# stm32f103cb_lcd32.net
KiCad netlist of a schematic drawn in EAGLE
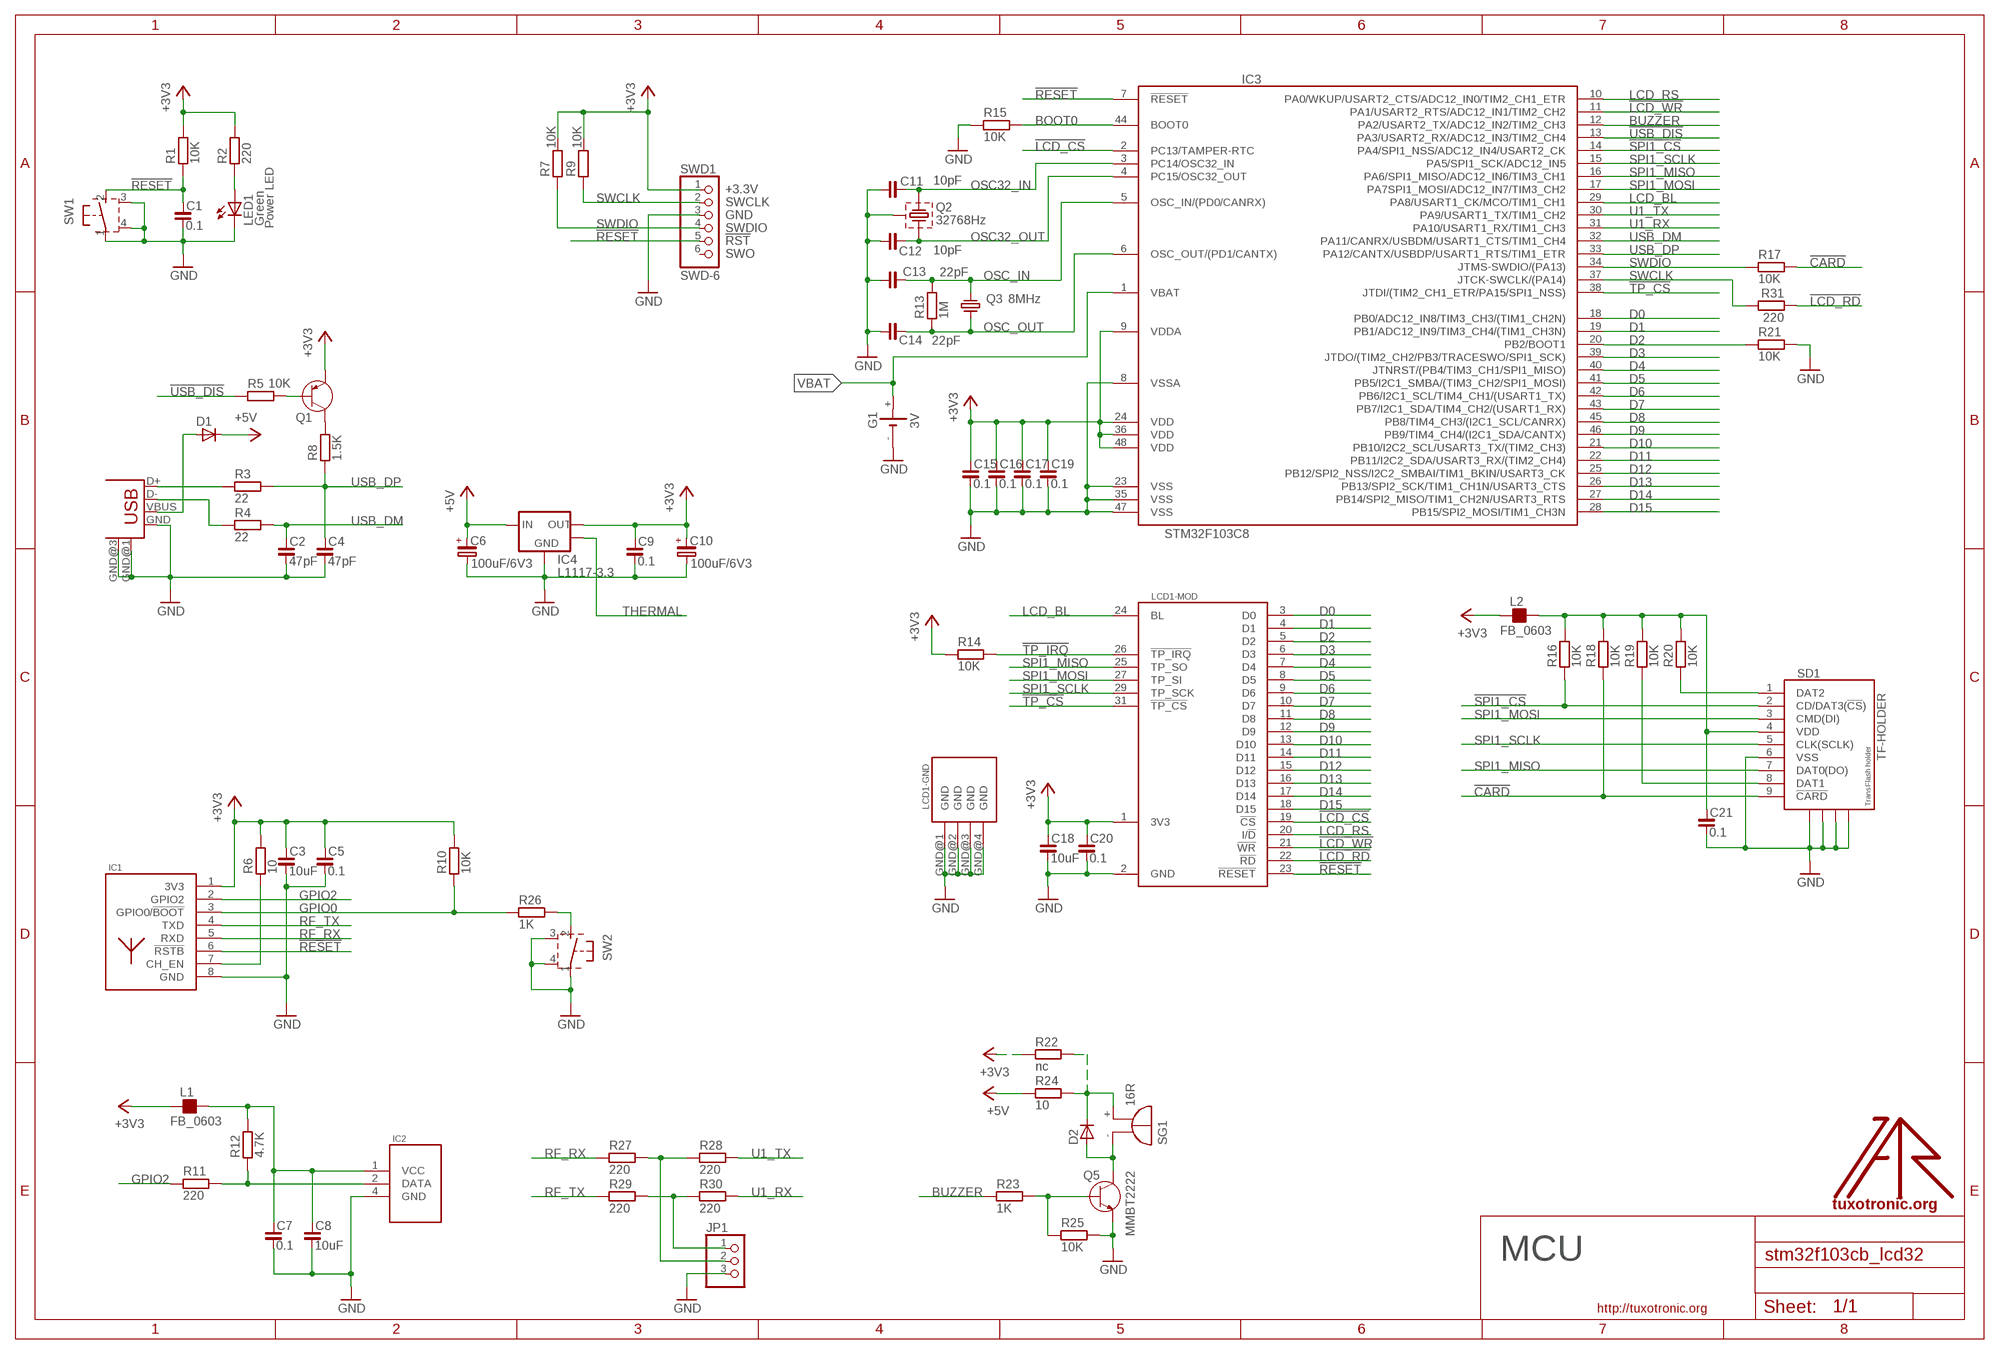
[diagram p0: schematic, sheet 1]

(export (version "E")
  (design (tool "Eeschema 10.0.6"))
  (components
    (comp (ref "C1")
      (value "0.1")
      (footprint "eagle-import:C0603")
      (libsource (lib "eagle-import") (part "C_0603"))
    )
    (comp (ref "C2")
      (value "47pF")
      (footprint "eagle-import:C0603")
      (libsource (lib "eagle-import") (part "C_0603"))
    )
    (comp (ref "C3")
      (value "10uF")
      (footprint "eagle-import:C0805")
      (libsource (lib "eagle-import") (part "C_0805"))
    )
    (comp (ref "C4")
      (value "47pF")
      (footprint "eagle-import:C0603")
      (libsource (lib "eagle-import") (part "C_0603"))
    )
    (comp (ref "C5")
      (value "0.1")
      (footprint "eagle-import:C0603")
      (libsource (lib "eagle-import") (part "C_0603"))
    )
    (comp (ref "C6")
      (value "100uF/6V3")
      (footprint "eagle-import:SMC_D")
      (libsource (lib "eagle-import") (part "CP_SMCD"))
    )
    (comp (ref "C7")
      (value "0.1")
      (footprint "eagle-import:C0603")
      (libsource (lib "eagle-import") (part "C_0603"))
    )
    (comp (ref "C8")
      (value "10uF")
      (footprint "eagle-import:C0805")
      (libsource (lib "eagle-import") (part "C_0805"))
    )
    (comp (ref "C9")
      (value "0.1")
      (footprint "eagle-import:C0805")
      (libsource (lib "eagle-import") (part "C_0805"))
    )
    (comp (ref "C10")
      (value "100uF/6V3")
      (footprint "eagle-import:SMC_D")
      (libsource (lib "eagle-import") (part "CP_SMCD"))
    )
    (comp (ref "C11")
      (value "10pF")
      (footprint "eagle-import:C0603")
      (libsource (lib "eagle-import") (part "C_0603"))
    )
    (comp (ref "C12")
      (value "10pF")
      (footprint "eagle-import:C0603")
      (libsource (lib "eagle-import") (part "C_0603"))
    )
    (comp (ref "C13")
      (value "22pF")
      (footprint "eagle-import:C0603")
      (libsource (lib "eagle-import") (part "C_0603"))
    )
    (comp (ref "C14")
      (value "22pF")
      (footprint "eagle-import:C0603")
      (libsource (lib "eagle-import") (part "C_0603"))
    )
    (comp (ref "C15")
      (value "0.1")
      (footprint "eagle-import:C0603")
      (libsource (lib "eagle-import") (part "C_0603"))
    )
    (comp (ref "C16")
      (value "0.1")
      (footprint "eagle-import:C0603")
      (libsource (lib "eagle-import") (part "C_0603"))
    )
    (comp (ref "C17")
      (value "0.1")
      (footprint "eagle-import:C0603")
      (libsource (lib "eagle-import") (part "C_0603"))
    )
    (comp (ref "C18")
      (value "10uF")
      (footprint "eagle-import:C0805")
      (libsource (lib "eagle-import") (part "C_0805"))
    )
    (comp (ref "C19")
      (value "0.1")
      (footprint "eagle-import:C0603")
      (libsource (lib "eagle-import") (part "C_0603"))
    )
    (comp (ref "C20")
      (value "0.1")
      (footprint "eagle-import:C0603")
      (libsource (lib "eagle-import") (part "C_0603"))
    )
    (comp (ref "C21")
      (value "0.1")
      (footprint "eagle-import:C0603")
      (libsource (lib "eagle-import") (part "C_0603"))
    )
    (comp (ref "D1")
      (value "D-SMB")
      (footprint "eagle-import:SMB")
      (libsource (lib "eagle-import") (part "D-SMB"))
    )
    (comp (ref "D2")
      (value "D-SOD-80")
      (footprint "eagle-import:SOD80")
      (libsource (lib "eagle-import") (part "D-SOD-80"))
    )
    (comp (ref "G1")
      (value "3V")
      (footprint "eagle-import:SMT1220")
      (libsource (lib "eagle-import") (part "1220SMT"))
    )
    (comp (ref "IC1")
      (value "ESP-11")
      (footprint "eagle-import:ESP11")
      (libsource (lib "eagle-import") (part "ESP-11"))
    )
    (comp (ref "IC2")
      (value "DHT22")
      (footprint "eagle-import:DHT")
      (libsource (lib "eagle-import") (part "DHT22"))
    )
    (comp (ref "IC3")
      (value "STM32F103C8")
      (footprint "eagle-import:LQFP48")
      (libsource (lib "eagle-import") (part "STM32F103C8"))
    )
    (comp (ref "IC4")
      (value "L1117-3.3")
      (footprint "eagle-import:SOT223-THP")
      (libsource (lib "eagle-import") (part "LM1117-THP"))
    )
    (comp (ref "JP1")
      (value "PINHD-1X3_2.54S")
      (footprint "eagle-import:1X03SMALL")
      (libsource (lib "eagle-import") (part "PINHD-1X3_2.54S"))
    )
    (comp (ref "L1")
      (value "FB_0603")
      (footprint "eagle-import:L0603")
      (libsource (lib "eagle-import") (part "FB_0603"))
    )
    (comp (ref "L2")
      (value "FB_0603")
      (footprint "eagle-import:L0603")
      (libsource (lib "eagle-import") (part "FB_0603"))
    )
    (comp (ref "LCD1")
      (value "YX32B")
      (footprint "eagle-import:YX32B")
      (libsource (lib "eagle-import") (part "YX32B"))
    )
    (comp (ref "LED1")
      (value "Green")
      (footprint "eagle-import:CHIP-LED0805")
      (libsource (lib "eagle-import") (part "LEDCHIP-LED0805"))
    )
    (comp (ref "LOGO1")
      (value "LOGO")
      (footprint "eagle-import:TT_LOGO")
      (libsource (lib "eagle-import") (part "LOGO"))
    )
    (comp (ref "Q1")
      (value "PNP-SOT23")
      (footprint "eagle-import:SOT23")
      (libsource (lib "eagle-import") (part "PNP-SOT23"))
    )
    (comp (ref "Q2")
      (value "32768Hz")
      (footprint "eagle-import:TC38H-G")
      (libsource (lib "eagle-import") (part "CRSTL3-"))
    )
    (comp (ref "Q3")
      (value "8MHz")
      (footprint "eagle-import:HC49_S")
      (libsource (lib "eagle-import") (part "CRYSTAL-HC49S"))
    )
    (comp (ref "Q5")
      (value "MMBT2222")
      (footprint "eagle-import:SOT23")
      (libsource (lib "eagle-import") (part "MMBT2222"))
    )
    (comp (ref "R1")
      (value "10K")
      (footprint "eagle-import:R0603")
      (libsource (lib "eagle-import") (part "R_0603"))
    )
    (comp (ref "R2")
      (value "220")
      (footprint "eagle-import:R0603")
      (libsource (lib "eagle-import") (part "R_0603"))
    )
    (comp (ref "R3")
      (value "22")
      (footprint "eagle-import:R0603")
      (libsource (lib "eagle-import") (part "R_0603"))
    )
    (comp (ref "R4")
      (value "22")
      (footprint "eagle-import:R0603")
      (libsource (lib "eagle-import") (part "R_0603"))
    )
    (comp (ref "R5")
      (value "10K")
      (footprint "eagle-import:R0603")
      (libsource (lib "eagle-import") (part "R_0603"))
    )
    (comp (ref "R6")
      (value "10")
      (footprint "eagle-import:R0603")
      (libsource (lib "eagle-import") (part "R_0603"))
    )
    (comp (ref "R7")
      (value "10K")
      (footprint "eagle-import:R0603")
      (libsource (lib "eagle-import") (part "R_0603"))
    )
    (comp (ref "R8")
      (value "1.5K")
      (footprint "eagle-import:R0603")
      (libsource (lib "eagle-import") (part "R_0603"))
    )
    (comp (ref "R9")
      (value "10K")
      (footprint "eagle-import:R0603")
      (libsource (lib "eagle-import") (part "R_0603"))
    )
    (comp (ref "R10")
      (value "10K")
      (footprint "eagle-import:R0603")
      (libsource (lib "eagle-import") (part "R_0603"))
    )
    (comp (ref "R11")
      (value "220")
      (footprint "eagle-import:R0603")
      (libsource (lib "eagle-import") (part "R_0603"))
    )
    (comp (ref "R12")
      (value "4.7K")
      (footprint "eagle-import:R0603")
      (libsource (lib "eagle-import") (part "R_0603"))
    )
    (comp (ref "R13")
      (value "1M")
      (footprint "eagle-import:R0603")
      (libsource (lib "eagle-import") (part "R_0603"))
    )
    (comp (ref "R14")
      (value "10K")
      (footprint "eagle-import:R0603")
      (libsource (lib "eagle-import") (part "R_0603"))
    )
    (comp (ref "R15")
      (value "10K")
      (footprint "eagle-import:R0603")
      (libsource (lib "eagle-import") (part "R_0603"))
    )
    (comp (ref "R16")
      (value "10K")
      (footprint "eagle-import:R0603")
      (libsource (lib "eagle-import") (part "R_0603"))
    )
    (comp (ref "R17")
      (value "10K")
      (footprint "eagle-import:R0603")
      (libsource (lib "eagle-import") (part "R_0603"))
    )
    (comp (ref "R18")
      (value "10K")
      (footprint "eagle-import:R0603")
      (libsource (lib "eagle-import") (part "R_0603"))
    )
    (comp (ref "R19")
      (value "10K")
      (footprint "eagle-import:R0603")
      (libsource (lib "eagle-import") (part "R_0603"))
    )
    (comp (ref "R20")
      (value "10K")
      (footprint "eagle-import:R0603")
      (libsource (lib "eagle-import") (part "R_0603"))
    )
    (comp (ref "R21")
      (value "10K")
      (footprint "eagle-import:R0603")
      (libsource (lib "eagle-import") (part "R_0603"))
    )
    (comp (ref "R22")
      (value "nc")
      (footprint "eagle-import:R0603")
      (libsource (lib "eagle-import") (part "R_0603"))
    )
    (comp (ref "R23")
      (value "1K")
      (footprint "eagle-import:R0603")
      (libsource (lib "eagle-import") (part "R_0603"))
    )
    (comp (ref "R24")
      (value "10")
      (footprint "eagle-import:R0603")
      (libsource (lib "eagle-import") (part "R_0603"))
    )
    (comp (ref "R25")
      (value "10K")
      (footprint "eagle-import:R0603")
      (libsource (lib "eagle-import") (part "R_0603"))
    )
    (comp (ref "R26")
      (value "1K")
      (footprint "eagle-import:R0603")
      (libsource (lib "eagle-import") (part "R_0603"))
    )
    (comp (ref "R27")
      (value "220")
      (footprint "eagle-import:R0603")
      (libsource (lib "eagle-import") (part "R_0603"))
    )
    (comp (ref "R28")
      (value "220")
      (footprint "eagle-import:R0603")
      (libsource (lib "eagle-import") (part "R_0603"))
    )
    (comp (ref "R29")
      (value "220")
      (footprint "eagle-import:R0603")
      (libsource (lib "eagle-import") (part "R_0603"))
    )
    (comp (ref "R30")
      (value "220")
      (footprint "eagle-import:R0603")
      (libsource (lib "eagle-import") (part "R_0603"))
    )
    (comp (ref "R31")
      (value "220")
      (footprint "eagle-import:R0603")
      (libsource (lib "eagle-import") (part "R_0603"))
    )
    (comp (ref "SD1")
      (value "TF-HOLDER")
      (footprint "eagle-import:TF-PULL")
      (libsource (lib "eagle-import") (part "TF-HOLDER"))
    )
    (comp (ref "SG1")
      (value "16R")
      (footprint "eagle-import:F_QMBIII")
      (libsource (lib "eagle-import") (part "F/QMBIII"))
    )
    (comp (ref "SW1")
      (value "31-XX")
      (footprint "eagle-import:B3F-31XX")
      (libsource (lib "eagle-import") (part "31-XX"))
    )
    (comp (ref "SW2")
      (value "31-XX")
      (footprint "eagle-import:B3F-31XX")
      (libsource (lib "eagle-import") (part "31-XX"))
    )
    (comp (ref "SWD1")
      (value "SWD-6")
      (footprint "eagle-import:JTAG6PIN")
      (libsource (lib "eagle-import") (part "SWD-6"))
    )
    (comp (ref "USB1")
      (value "USB-MB-S")
      (footprint "eagle-import:USB-MB-S")
      (libsource (lib "eagle-import") (part "USB-MB-S"))
    )
  )
  (nets
    (net (code "1") (name "+3V3") (class "Default")
      (node (ref "C10") (pin "+") (pinfunction "+_+") (pintype "passive"))
      (node (ref "C15") (pin "1") (pinfunction "1_1") (pintype "passive"))
      (node (ref "C16") (pin "1") (pinfunction "1_1") (pintype "passive"))
      (node (ref "C17") (pin "1") (pinfunction "1_1") (pintype "passive"))
      (node (ref "C18") (pin "1") (pinfunction "1_1") (pintype "passive"))
      (node (ref "C19") (pin "1") (pinfunction "1_1") (pintype "passive"))
      (node (ref "C20") (pin "1") (pinfunction "1_1") (pintype "passive"))
      (node (ref "C3") (pin "1") (pinfunction "1_1") (pintype "passive"))
      (node (ref "C5") (pin "1") (pinfunction "1_1") (pintype "passive"))
      (node (ref "C9") (pin "1") (pinfunction "1_1") (pintype "passive"))
      (node (ref "IC1") (pin "1") (pinfunction "3V3_1") (pintype "power_in"))
      (node (ref "IC3") (pin "24") (pinfunction "VDD_24") (pintype "power_in"))
      (node (ref "IC3") (pin "36") (pinfunction "VDD_36") (pintype "power_in"))
      (node (ref "IC3") (pin "48") (pinfunction "VDD_48") (pintype "power_in"))
      (node (ref "IC3") (pin "9") (pinfunction "VDDA_9") (pintype "power_in"))
      (node (ref "IC4") (pin "2") (pinfunction "OUT_2") (pintype "power_in"))
      (node (ref "L1") (pin "1") (pinfunction "1_1") (pintype "passive"))
      (node (ref "L2") (pin "1") (pinfunction "1_1") (pintype "passive"))
      (node (ref "LCD1") (pin "1") (pinfunction "3V3_1") (pintype "power_in"))
      (node (ref "Q1") (pin "2") (pinfunction "E_2") (pintype "passive"))
      (node (ref "R1") (pin "2") (pinfunction "2_2") (pintype "passive"))
      (node (ref "R10") (pin "2") (pinfunction "2_2") (pintype "passive"))
      (node (ref "R14") (pin "1") (pinfunction "1_1") (pintype "passive"))
      (node (ref "R2") (pin "2") (pinfunction "2_2") (pintype "passive"))
      (node (ref "R22") (pin "1") (pinfunction "1_1") (pintype "passive"))
      (node (ref "R6") (pin "2") (pinfunction "2_2") (pintype "passive"))
      (node (ref "R7") (pin "2") (pinfunction "2_2") (pintype "passive"))
      (node (ref "R9") (pin "2") (pinfunction "2_2") (pintype "passive"))
      (node (ref "SWD1") (pin "1") (pinfunction "1_1") (pintype "passive"))
    )
    (net (code "2") (name "+5V") (class "Default")
      (node (ref "C6") (pin "+") (pinfunction "+_+") (pintype "passive"))
      (node (ref "D1") (pin "1") (pinfunction "C_1") (pintype "passive"))
      (node (ref "IC4") (pin "3") (pinfunction "IN_3") (pintype "power_in"))
      (node (ref "R24") (pin "1") (pinfunction "1_1") (pintype "passive"))
    )
    (net (code "3") (name "/BOOT0") (class "Default")
      (node (ref "IC3") (pin "44") (pinfunction "BOOT0_44") (pintype "input"))
      (node (ref "R15") (pin "2") (pinfunction "2_2") (pintype "passive"))
    )
    (net (code "4") (name "/BUZZER") (class "Default")
      (node (ref "IC3") (pin "12") (pinfunction "PA2/USART2_TX/ADC12_IN2/TIM2_CH3_12") (pintype "bidirectional"))
      (node (ref "R23") (pin "1") (pinfunction "1_1") (pintype "passive"))
    )
    (net (code "5") (name "/D0") (class "Default")
      (node (ref "IC3") (pin "18") (pinfunction "PB0/ADC12_IN8/TIM3_CH3/(TIM1_CH2N)_18") (pintype "bidirectional"))
      (node (ref "LCD1") (pin "3") (pinfunction "D0_3") (pintype "bidirectional"))
    )
    (net (code "6") (name "/D1") (class "Default")
      (node (ref "IC3") (pin "19") (pinfunction "PB1/ADC12_IN9/TIM3_CH4/(TIM1_CH3N)_19") (pintype "bidirectional"))
      (node (ref "LCD1") (pin "4") (pinfunction "D1_4") (pintype "bidirectional"))
    )
    (net (code "7") (name "/D2") (class "Default")
      (node (ref "IC3") (pin "20") (pinfunction "PB2/BOOT1_20") (pintype "bidirectional"))
      (node (ref "LCD1") (pin "5") (pinfunction "D2_5") (pintype "bidirectional"))
      (node (ref "R21") (pin "1") (pinfunction "1_1") (pintype "passive"))
    )
    (net (code "8") (name "/D3") (class "Default")
      (node (ref "IC3") (pin "39") (pinfunction "JTDO/(TIM2_CH2/PB3/TRACESWO/SPI1_SCK)_39") (pintype "bidirectional"))
      (node (ref "LCD1") (pin "6") (pinfunction "D3_6") (pintype "bidirectional"))
    )
    (net (code "9") (name "/D4") (class "Default")
      (node (ref "IC3") (pin "40") (pinfunction "JTNRST/(PB4/TIM3_CH1/SPI1_MISO)_40") (pintype "bidirectional"))
      (node (ref "LCD1") (pin "7") (pinfunction "D4_7") (pintype "bidirectional"))
    )
    (net (code "10") (name "/D5") (class "Default")
      (node (ref "IC3") (pin "41") (pinfunction "PB5/I2C1_SMBA/(TIM3_CH2/SPI1_MOSI)_41") (pintype "bidirectional"))
      (node (ref "LCD1") (pin "8") (pinfunction "D5_8") (pintype "bidirectional"))
    )
    (net (code "11") (name "/D6") (class "Default")
      (node (ref "IC3") (pin "42") (pinfunction "PB6/I2C1_SCL/TIM4_CH1/(USART1_TX)_42") (pintype "bidirectional"))
      (node (ref "LCD1") (pin "9") (pinfunction "D6_9") (pintype "bidirectional"))
    )
    (net (code "12") (name "/D7") (class "Default")
      (node (ref "IC3") (pin "43") (pinfunction "PB7/I2C1_SDA/TIM4_CH2/(USART1_RX)_43") (pintype "bidirectional"))
      (node (ref "LCD1") (pin "10") (pinfunction "D7_10") (pintype "bidirectional"))
    )
    (net (code "13") (name "/D8") (class "Default")
      (node (ref "IC3") (pin "45") (pinfunction "PB8/TIM4_CH3/(I2C1_SCL/CANRX)_45") (pintype "bidirectional"))
      (node (ref "LCD1") (pin "11") (pinfunction "D8_11") (pintype "bidirectional"))
    )
    (net (code "14") (name "/D9") (class "Default")
      (node (ref "IC3") (pin "46") (pinfunction "PB9/TIM4_CH4/(I2C1_SDA/CANTX)_46") (pintype "bidirectional"))
      (node (ref "LCD1") (pin "12") (pinfunction "D9_12") (pintype "bidirectional"))
    )
    (net (code "15") (name "/D10") (class "Default")
      (node (ref "IC3") (pin "21") (pinfunction "PB10/I2C2_SCL/USART3_TX/(TIM2_CH3)_21") (pintype "bidirectional"))
      (node (ref "LCD1") (pin "13") (pinfunction "D10_13") (pintype "bidirectional"))
    )
    (net (code "16") (name "/D11") (class "Default")
      (node (ref "IC3") (pin "22") (pinfunction "PB11/I2C2_SDA/USART3_RX/(TIM2_CH4)_22") (pintype "bidirectional"))
      (node (ref "LCD1") (pin "14") (pinfunction "D11_14") (pintype "bidirectional"))
    )
    (net (code "17") (name "/D12") (class "Default")
      (node (ref "IC3") (pin "25") (pinfunction "PB12/SPI2_NSS/I2C2_SMBAI/TIM1_BKIN/USART3_CK_25") (pintype "bidirectional"))
      (node (ref "LCD1") (pin "15") (pinfunction "D12_15") (pintype "bidirectional"))
    )
    (net (code "18") (name "/D13") (class "Default")
      (node (ref "IC3") (pin "26") (pinfunction "PB13/SPI2_SCK/TIM1_CH1N/USART3_CTS_26") (pintype "bidirectional"))
      (node (ref "LCD1") (pin "16") (pinfunction "D13_16") (pintype "bidirectional"))
    )
    (net (code "19") (name "/D14") (class "Default")
      (node (ref "IC3") (pin "27") (pinfunction "PB14/SPI2_MISO/TIM1_CH2N/USART3_RTS_27") (pintype "bidirectional"))
      (node (ref "LCD1") (pin "17") (pinfunction "D14_17") (pintype "bidirectional"))
    )
    (net (code "20") (name "/D15") (class "Default")
      (node (ref "IC3") (pin "28") (pinfunction "PB15/SPI2_MOSI/TIM1_CH3N_28") (pintype "bidirectional"))
      (node (ref "LCD1") (pin "18") (pinfunction "D15_18") (pintype "bidirectional"))
    )
    (net (code "21") (name "/GPIO0") (class "Default")
      (node (ref "IC1") (pin "3") (pinfunction "GPIO0/~{BOOT}_3") (pintype "bidirectional"))
      (node (ref "R10") (pin "1") (pinfunction "1_1") (pintype "passive"))
      (node (ref "R26") (pin "1") (pinfunction "1_1") (pintype "passive"))
    )
    (net (code "22") (name "/GPIO2") (class "Default")
      (node (ref "IC1") (pin "2") (pinfunction "GPIO2_2") (pintype "bidirectional"))
      (node (ref "R11") (pin "1") (pinfunction "1_1") (pintype "passive"))
    )
    (net (code "23") (name "/LCD_BL") (class "Default")
      (node (ref "IC3") (pin "29") (pinfunction "PA8/USART1_CK/MCO/TIM1_CH1_29") (pintype "bidirectional"))
      (node (ref "LCD1") (pin "24") (pinfunction "BL_24") (pintype "input"))
    )
    (net (code "24") (name "/LCD_RS") (class "Default")
      (node (ref "IC3") (pin "10") (pinfunction "PA0/WKUP/USART2_CTS/ADC12_IN0/TIM2_CH1_ETR_10") (pintype "bidirectional"))
      (node (ref "LCD1") (pin "20") (pinfunction "I/~{D}_20") (pintype "input"))
    )
    (net (code "25") (name "/OSC32_IN") (class "Default")
      (node (ref "C11") (pin "1") (pinfunction "1_1") (pintype "passive"))
      (node (ref "IC3") (pin "3") (pinfunction "PC14/OSC32_IN_3") (pintype "bidirectional"))
      (node (ref "Q2") (pin "2") (pinfunction "2_2") (pintype "passive"))
    )
    (net (code "26") (name "/OSC32_OUT") (class "Default")
      (node (ref "C12") (pin "1") (pinfunction "1_1") (pintype "passive"))
      (node (ref "IC3") (pin "4") (pinfunction "PC15/OSC32_OUT_4") (pintype "bidirectional"))
      (node (ref "Q2") (pin "1") (pinfunction "1_1") (pintype "passive"))
    )
    (net (code "27") (name "/OSC_IN") (class "Default")
      (node (ref "C13") (pin "1") (pinfunction "1_1") (pintype "passive"))
      (node (ref "IC3") (pin "5") (pinfunction "OSC_IN/(PD0/CANRX)_5") (pintype "input"))
      (node (ref "Q3") (pin "1") (pinfunction "1_1") (pintype "passive"))
      (node (ref "R13") (pin "2") (pinfunction "2_2") (pintype "passive"))
    )
    (net (code "28") (name "/OSC_OUT") (class "Default")
      (node (ref "C14") (pin "1") (pinfunction "1_1") (pintype "passive"))
      (node (ref "IC3") (pin "6") (pinfunction "OSC_OUT/(PD1/CANTX)_6") (pintype "output"))
      (node (ref "Q3") (pin "2") (pinfunction "2_2") (pintype "passive"))
      (node (ref "R13") (pin "1") (pinfunction "1_1") (pintype "passive"))
    )
    (net (code "29") (name "/RF_RX") (class "Default")
      (node (ref "IC1") (pin "5") (pinfunction "RXD_5") (pintype "input"))
      (node (ref "R27") (pin "1") (pinfunction "1_1") (pintype "passive"))
    )
    (net (code "30") (name "/RF_TX") (class "Default")
      (node (ref "IC1") (pin "4") (pinfunction "TXD_4") (pintype "output"))
      (node (ref "R29") (pin "1") (pinfunction "1_1") (pintype "passive"))
    )
    (net (code "31") (name "/SPI1_MISO") (class "Default")
      (node (ref "IC3") (pin "16") (pinfunction "PA6/SPI1_MISO/ADC12_IN6/TIM3_CH1_16") (pintype "bidirectional"))
      (node (ref "LCD1") (pin "25") (pinfunction "TP_SO_25") (pintype "output"))
      (node (ref "SD1") (pin "7") (pinfunction "DAT0(DO)_7") (pintype "bidirectional"))
    )
    (net (code "32") (name "/SPI1_MOSI") (class "Default")
      (node (ref "IC3") (pin "17") (pinfunction "PA7SPI1_MOSI/ADC12_IN7/TIM3_CH2_17") (pintype "bidirectional"))
      (node (ref "LCD1") (pin "27") (pinfunction "TP_SI_27") (pintype "input"))
      (node (ref "SD1") (pin "3") (pinfunction "CMD(DI)_3") (pintype "bidirectional"))
    )
    (net (code "33") (name "/SPI1_SCLK") (class "Default")
      (node (ref "IC3") (pin "15") (pinfunction "PA5/SPI1_SCK/ADC12_IN5_15") (pintype "bidirectional"))
      (node (ref "LCD1") (pin "29") (pinfunction "TP_SCK_29") (pintype "input"))
      (node (ref "SD1") (pin "5") (pinfunction "CLK(SCLK)_5") (pintype "input"))
    )
    (net (code "34") (name "/SWCLK") (class "Default")
      (node (ref "IC3") (pin "37") (pinfunction "JTCK-SWCLK/(PA14)_37") (pintype "bidirectional"))
      (node (ref "R31") (pin "2") (pinfunction "2_2") (pintype "passive"))
      (node (ref "R9") (pin "1") (pinfunction "1_1") (pintype "passive"))
      (node (ref "SWD1") (pin "2") (pinfunction "2_2") (pintype "passive"))
    )
    (net (code "35") (name "/SWDIO") (class "Default")
      (node (ref "IC3") (pin "34") (pinfunction "JTMS-SWDIO/(PA13)_34") (pintype "bidirectional"))
      (node (ref "R17") (pin "1") (pinfunction "1_1") (pintype "passive"))
      (node (ref "R7") (pin "1") (pinfunction "1_1") (pintype "passive"))
      (node (ref "SWD1") (pin "4") (pinfunction "4_4") (pintype "passive"))
    )
    (net (code "36") (name "/THERMAL") (class "Default")
      (node (ref "IC4") (pin "4") (pinfunction "MASS_4") (pintype "passive"))
    )
    (net (code "37") (name "/U1_RX") (class "Default")
      (node (ref "IC3") (pin "31") (pinfunction "PA10/USART1_RX/TIM1_CH3_31") (pintype "bidirectional"))
      (node (ref "R30") (pin "2") (pinfunction "2_2") (pintype "passive"))
    )
    (net (code "38") (name "/U1_TX") (class "Default")
      (node (ref "IC3") (pin "30") (pinfunction "PA9/USART1_TX/TIM1_CH2_30") (pintype "bidirectional"))
      (node (ref "R28") (pin "2") (pinfunction "2_2") (pintype "passive"))
    )
    (net (code "39") (name "/USB_DM") (class "Default")
      (node (ref "C2") (pin "1") (pinfunction "1_1") (pintype "passive"))
      (node (ref "IC3") (pin "32") (pinfunction "PA11/CANRX/USBDM/USART1_CTS/TIM1_CH4_32") (pintype "bidirectional"))
      (node (ref "R4") (pin "2") (pinfunction "2_2") (pintype "passive"))
    )
    (net (code "40") (name "/USB_DP") (class "Default")
      (node (ref "C4") (pin "1") (pinfunction "1_1") (pintype "passive"))
      (node (ref "IC3") (pin "33") (pinfunction "PA12/CANTX/USBDP/USART1_RTS/TIM1_ETR_33") (pintype "bidirectional"))
      (node (ref "R3") (pin "2") (pinfunction "2_2") (pintype "passive"))
      (node (ref "R8") (pin "1") (pinfunction "1_1") (pintype "passive"))
    )
    (net (code "41") (name "/~{CARD}") (class "Default")
      (node (ref "R17") (pin "2") (pinfunction "2_2") (pintype "passive"))
      (node (ref "R18") (pin "1") (pinfunction "1_1") (pintype "passive"))
      (node (ref "SD1") (pin "9") (pinfunction "~{CARD}_9") (pintype "passive"))
    )
    (net (code "42") (name "/~{LCD_CS}") (class "Default")
      (node (ref "IC3") (pin "2") (pinfunction "PC13/TAMPER-RTC_2") (pintype "bidirectional"))
      (node (ref "LCD1") (pin "19") (pinfunction "~{CS}_19") (pintype "input"))
    )
    (net (code "43") (name "/~{LCD_RD}") (class "Default")
      (node (ref "LCD1") (pin "22") (pinfunction "~{RD}_22") (pintype "input"))
      (node (ref "R31") (pin "1") (pinfunction "1_1") (pintype "passive"))
    )
    (net (code "44") (name "/~{LCD_WR}") (class "Default")
      (node (ref "IC3") (pin "11") (pinfunction "PA1/USART2_RTS/ADC12_IN1/TIM2_CH2_11") (pintype "bidirectional"))
      (node (ref "LCD1") (pin "21") (pinfunction "~{WR}_21") (pintype "input"))
    )
    (net (code "45") (name "/~{RESET}") (class "Default")
      (node (ref "C1") (pin "1") (pinfunction "1_1") (pintype "passive"))
      (node (ref "IC1") (pin "6") (pinfunction "~{RSTB}_6") (pintype "input"))
      (node (ref "IC3") (pin "7") (pinfunction "~{RESET}_7") (pintype "input"))
      (node (ref "LCD1") (pin "23") (pinfunction "~{RESET}_23") (pintype "input"))
      (node (ref "R1") (pin "1") (pinfunction "1_1") (pintype "passive"))
      (node (ref "SW1") (pin "2") (pinfunction "S_2") (pintype "passive"))
      (node (ref "SWD1") (pin "5") (pinfunction "5_5") (pintype "passive"))
    )
    (net (code "46") (name "/~{SPI1_CS}") (class "Default")
      (node (ref "IC3") (pin "14") (pinfunction "PA4/SPI1_NSS/ADC12_IN4/USART2_CK_14") (pintype "bidirectional"))
      (node (ref "R16") (pin "1") (pinfunction "1_1") (pintype "passive"))
      (node (ref "SD1") (pin "2") (pinfunction "CD/DAT3(~{CS})_2") (pintype "bidirectional"))
    )
    (net (code "47") (name "/~{TP_CS}") (class "Default")
      (node (ref "IC3") (pin "38") (pinfunction "JTDI/(TIM2_CH1_ETR/PA15/SPI1_NSS)_38") (pintype "bidirectional"))
      (node (ref "LCD1") (pin "31") (pinfunction "~{TP_CS}_31") (pintype "input"))
    )
    (net (code "48") (name "/~{TP_IRQ}") (class "Default")
      (node (ref "LCD1") (pin "26") (pinfunction "~{TP_IRQ}_26") (pintype "output"))
      (node (ref "R14") (pin "2") (pinfunction "2_2") (pintype "passive"))
    )
    (net (code "49") (name "/~{USB_DIS}") (class "Default")
      (node (ref "IC3") (pin "13") (pinfunction "PA3/USART2_RX/ADC12_IN3/TIM2_CH4_13") (pintype "bidirectional"))
      (node (ref "R5") (pin "1") (pinfunction "1_1") (pintype "passive"))
    )
    (net (code "50") (name "GND") (class "Default")
      (node (ref "C1") (pin "2") (pinfunction "2_2") (pintype "passive"))
      (node (ref "C10") (pin "-") (pinfunction "-_-") (pintype "passive"))
      (node (ref "C11") (pin "2") (pinfunction "2_2") (pintype "passive"))
      (node (ref "C12") (pin "2") (pinfunction "2_2") (pintype "passive"))
      (node (ref "C13") (pin "2") (pinfunction "2_2") (pintype "passive"))
      (node (ref "C14") (pin "2") (pinfunction "2_2") (pintype "passive"))
      (node (ref "C15") (pin "2") (pinfunction "2_2") (pintype "passive"))
      (node (ref "C16") (pin "2") (pinfunction "2_2") (pintype "passive"))
      (node (ref "C17") (pin "2") (pinfunction "2_2") (pintype "passive"))
      (node (ref "C18") (pin "2") (pinfunction "2_2") (pintype "passive"))
      (node (ref "C19") (pin "2") (pinfunction "2_2") (pintype "passive"))
      (node (ref "C2") (pin "2") (pinfunction "2_2") (pintype "passive"))
      (node (ref "C20") (pin "2") (pinfunction "2_2") (pintype "passive"))
      (node (ref "C21") (pin "2") (pinfunction "2_2") (pintype "passive"))
      (node (ref "C3") (pin "2") (pinfunction "2_2") (pintype "passive"))
      (node (ref "C4") (pin "2") (pinfunction "2_2") (pintype "passive"))
      (node (ref "C5") (pin "2") (pinfunction "2_2") (pintype "passive"))
      (node (ref "C6") (pin "-") (pinfunction "-_-") (pintype "passive"))
      (node (ref "C7") (pin "2") (pinfunction "2_2") (pintype "passive"))
      (node (ref "C8") (pin "2") (pinfunction "2_2") (pintype "passive"))
      (node (ref "C9") (pin "2") (pinfunction "2_2") (pintype "passive"))
      (node (ref "G1") (pin "-") (pinfunction "-_-") (pintype "passive"))
      (node (ref "IC1") (pin "8") (pinfunction "GND_8") (pintype "power_in"))
      (node (ref "IC2") (pin "4") (pinfunction "GND_4") (pintype "power_in"))
      (node (ref "IC3") (pin "23") (pinfunction "VSS_23") (pintype "power_in"))
      (node (ref "IC3") (pin "35") (pinfunction "VSS_35") (pintype "power_in"))
      (node (ref "IC3") (pin "47") (pinfunction "VSS_47") (pintype "power_in"))
      (node (ref "IC3") (pin "8") (pinfunction "VSSA_8") (pintype "power_in"))
      (node (ref "IC4") (pin "1") (pinfunction "GND_1") (pintype "power_in"))
      (node (ref "JP1") (pin "3") (pinfunction "3_3") (pintype "passive"))
      (node (ref "LCD1") (pin "2") (pinfunction "GND_2") (pintype "power_in"))
      (node (ref "LCD1") (pin "GND@1") (pinfunction "GND_GND@1") (pintype "power_in"))
      (node (ref "LCD1") (pin "GND@2") (pinfunction "GND_GND@2") (pintype "power_in"))
      (node (ref "LCD1") (pin "GND@3") (pinfunction "GND_GND@3") (pintype "power_in"))
      (node (ref "LCD1") (pin "GND@4") (pinfunction "GND_GND@4") (pintype "power_in"))
      (node (ref "LED1") (pin "C") (pinfunction "C_C") (pintype "passive"))
      (node (ref "Q2") (pin "GND") (pinfunction "P$1_GND") (pintype "passive"))
      (node (ref "Q5") (pin "2") (pinfunction "E_2") (pintype "passive"))
      (node (ref "R15") (pin "1") (pinfunction "1_1") (pintype "passive"))
      (node (ref "R21") (pin "2") (pinfunction "2_2") (pintype "passive"))
      (node (ref "R25") (pin "2") (pinfunction "2_2") (pintype "passive"))
      (node (ref "SD1") (pin "6") (pinfunction "VSS_6") (pintype "power_in"))
      (node (ref "SD1") (pin "S1") (pinfunction "S1_S1") (pintype "passive"))
      (node (ref "SD1") (pin "S2") (pinfunction "S2_S2") (pintype "passive"))
      (node (ref "SD1") (pin "S3") (pinfunction "S3_S3") (pintype "passive"))
      (node (ref "SD1") (pin "S4") (pinfunction "S4_S4") (pintype "passive"))
      (node (ref "SW1") (pin "1") (pinfunction "P_1") (pintype "passive"))
      (node (ref "SW1") (pin "3") (pinfunction "GND1_3") (pintype "passive"))
      (node (ref "SW1") (pin "4") (pinfunction "GND2_4") (pintype "passive"))
      (node (ref "SW2") (pin "1") (pinfunction "P_1") (pintype "passive"))
      (node (ref "SW2") (pin "3") (pinfunction "GND1_3") (pintype "passive"))
      (node (ref "SW2") (pin "4") (pinfunction "GND2_4") (pintype "passive"))
      (node (ref "SWD1") (pin "3") (pinfunction "3_3") (pintype "passive"))
      (node (ref "USB1") (pin "GND") (pinfunction "GND_GND") (pintype "bidirectional"))
      (node (ref "USB1") (pin "GND@1") (pinfunction "GND_GND@1") (pintype "bidirectional"))
      (node (ref "USB1") (pin "GND@3") (pinfunction "GND_GND@3") (pintype "bidirectional"))
    )
    (net (code "51") (name "Net-(D1-A)") (class "Default")
      (node (ref "D1") (pin "2") (pinfunction "A_2") (pintype "passive"))
      (node (ref "USB1") (pin "VBUS") (pinfunction "VBUS_VBUS") (pintype "bidirectional"))
    )
    (net (code "52") (name "Net-(D2-A)") (class "Default")
      (node (ref "D2") (pin "2") (pinfunction "A_2") (pintype "passive"))
      (node (ref "Q5") (pin "3") (pinfunction "C_3") (pintype "passive"))
      (node (ref "SG1") (pin "-") (pinfunction "+_-") (pintype "passive"))
    )
    (net (code "53") (name "Net-(D2-C)") (class "Default")
      (node (ref "D2") (pin "1") (pinfunction "C_1") (pintype "passive"))
      (node (ref "R22") (pin "2") (pinfunction "2_2") (pintype "passive"))
      (node (ref "R24") (pin "2") (pinfunction "2_2") (pintype "passive"))
      (node (ref "SG1") (pin "+") (pinfunction "-_+") (pintype "passive"))
    )
    (net (code "54") (name "Net-(IC1-CH_EN)") (class "Default")
      (node (ref "IC1") (pin "7") (pinfunction "CH_EN_7") (pintype "input"))
      (node (ref "R6") (pin "1") (pinfunction "1_1") (pintype "passive"))
    )
    (net (code "55") (name "Net-(IC2-DATA)") (class "Default")
      (node (ref "IC2") (pin "2") (pinfunction "DATA_2") (pintype "bidirectional"))
      (node (ref "R11") (pin "2") (pinfunction "2_2") (pintype "passive"))
      (node (ref "R12") (pin "1") (pinfunction "1_1") (pintype "passive"))
    )
    (net (code "56") (name "Net-(IC2-VCC)") (class "Default")
      (node (ref "C7") (pin "1") (pinfunction "1_1") (pintype "passive"))
      (node (ref "C8") (pin "1") (pinfunction "1_1") (pintype "passive"))
      (node (ref "IC2") (pin "1") (pinfunction "VCC_1") (pintype "power_in"))
      (node (ref "L1") (pin "2") (pinfunction "2_2") (pintype "passive"))
      (node (ref "R12") (pin "2") (pinfunction "2_2") (pintype "passive"))
    )
    (net (code "57") (name "Net-(JP1-Pad1)") (class "Default")
      (node (ref "JP1") (pin "1") (pinfunction "1_1") (pintype "passive"))
      (node (ref "R29") (pin "2") (pinfunction "2_2") (pintype "passive"))
      (node (ref "R30") (pin "1") (pinfunction "1_1") (pintype "passive"))
    )
    (net (code "58") (name "Net-(JP1-Pad2)") (class "Default")
      (node (ref "JP1") (pin "2") (pinfunction "2_2") (pintype "passive"))
      (node (ref "R27") (pin "2") (pinfunction "2_2") (pintype "passive"))
      (node (ref "R28") (pin "1") (pinfunction "1_1") (pintype "passive"))
    )
    (net (code "59") (name "Net-(LED1-PadA)") (class "Default")
      (node (ref "LED1") (pin "A") (pinfunction "A_A") (pintype "passive"))
      (node (ref "R2") (pin "1") (pinfunction "1_1") (pintype "passive"))
    )
    (net (code "60") (name "Net-(Q1-B)") (class "Default")
      (node (ref "Q1") (pin "1") (pinfunction "B_1") (pintype "passive"))
      (node (ref "R5") (pin "2") (pinfunction "2_2") (pintype "passive"))
    )
    (net (code "61") (name "Net-(Q1-C)") (class "Default")
      (node (ref "Q1") (pin "3") (pinfunction "C_3") (pintype "passive"))
      (node (ref "R8") (pin "2") (pinfunction "2_2") (pintype "passive"))
    )
    (net (code "62") (name "Net-(Q5-B)") (class "Default")
      (node (ref "Q5") (pin "1") (pinfunction "B_1") (pintype "passive"))
      (node (ref "R23") (pin "2") (pinfunction "2_2") (pintype "passive"))
      (node (ref "R25") (pin "1") (pinfunction "1_1") (pintype "passive"))
    )
    (net (code "63") (name "Net-(R3-Pad1)") (class "Default")
      (node (ref "R3") (pin "1") (pinfunction "1_1") (pintype "passive"))
      (node (ref "USB1") (pin "D+") (pinfunction "D+_D+") (pintype "bidirectional"))
    )
    (net (code "64") (name "Net-(R4-Pad1)") (class "Default")
      (node (ref "R4") (pin "1") (pinfunction "1_1") (pintype "passive"))
      (node (ref "USB1") (pin "D-") (pinfunction "D-_D-") (pintype "bidirectional"))
    )
    (net (code "65") (name "Net-(SD1-DAT1)") (class "Default")
      (node (ref "R19") (pin "1") (pinfunction "1_1") (pintype "passive"))
      (node (ref "SD1") (pin "8") (pinfunction "DAT1_8") (pintype "bidirectional"))
    )
    (net (code "66") (name "Net-(SD1-DAT2)") (class "Default")
      (node (ref "R20") (pin "1") (pinfunction "1_1") (pintype "passive"))
      (node (ref "SD1") (pin "1") (pinfunction "DAT2_1") (pintype "bidirectional"))
    )
    (net (code "67") (name "Net-(SD1-VDD)") (class "Default")
      (node (ref "C21") (pin "1") (pinfunction "1_1") (pintype "passive"))
      (node (ref "L2") (pin "2") (pinfunction "2_2") (pintype "passive"))
      (node (ref "R16") (pin "2") (pinfunction "2_2") (pintype "passive"))
      (node (ref "R18") (pin "2") (pinfunction "2_2") (pintype "passive"))
      (node (ref "R19") (pin "2") (pinfunction "2_2") (pintype "passive"))
      (node (ref "R20") (pin "2") (pinfunction "2_2") (pintype "passive"))
      (node (ref "SD1") (pin "4") (pinfunction "VDD_4") (pintype "power_in"))
    )
    (net (code "68") (name "Net-(SW2-S)") (class "Default")
      (node (ref "R26") (pin "2") (pinfunction "2_2") (pintype "passive"))
      (node (ref "SW2") (pin "2") (pinfunction "S_2") (pintype "passive"))
    )
    (net (code "69") (name "VBAT") (class "Default")
      (node (ref "G1") (pin "+") (pinfunction "+_+") (pintype "passive"))
      (node (ref "IC3") (pin "1") (pinfunction "VBAT_1") (pintype "power_in"))
    )
    (net (code "70") (name "unconnected-(SWD1-Pad6)") (class "Default")
      (node (ref "SWD1") (pin "6") (pinfunction "6_6") (pintype "passive"))
    )
  )
)
